# soundboard-qtpy-usd-dac-smaller-v02.net
KiCad netlist of a schematic drawn in EAGLE
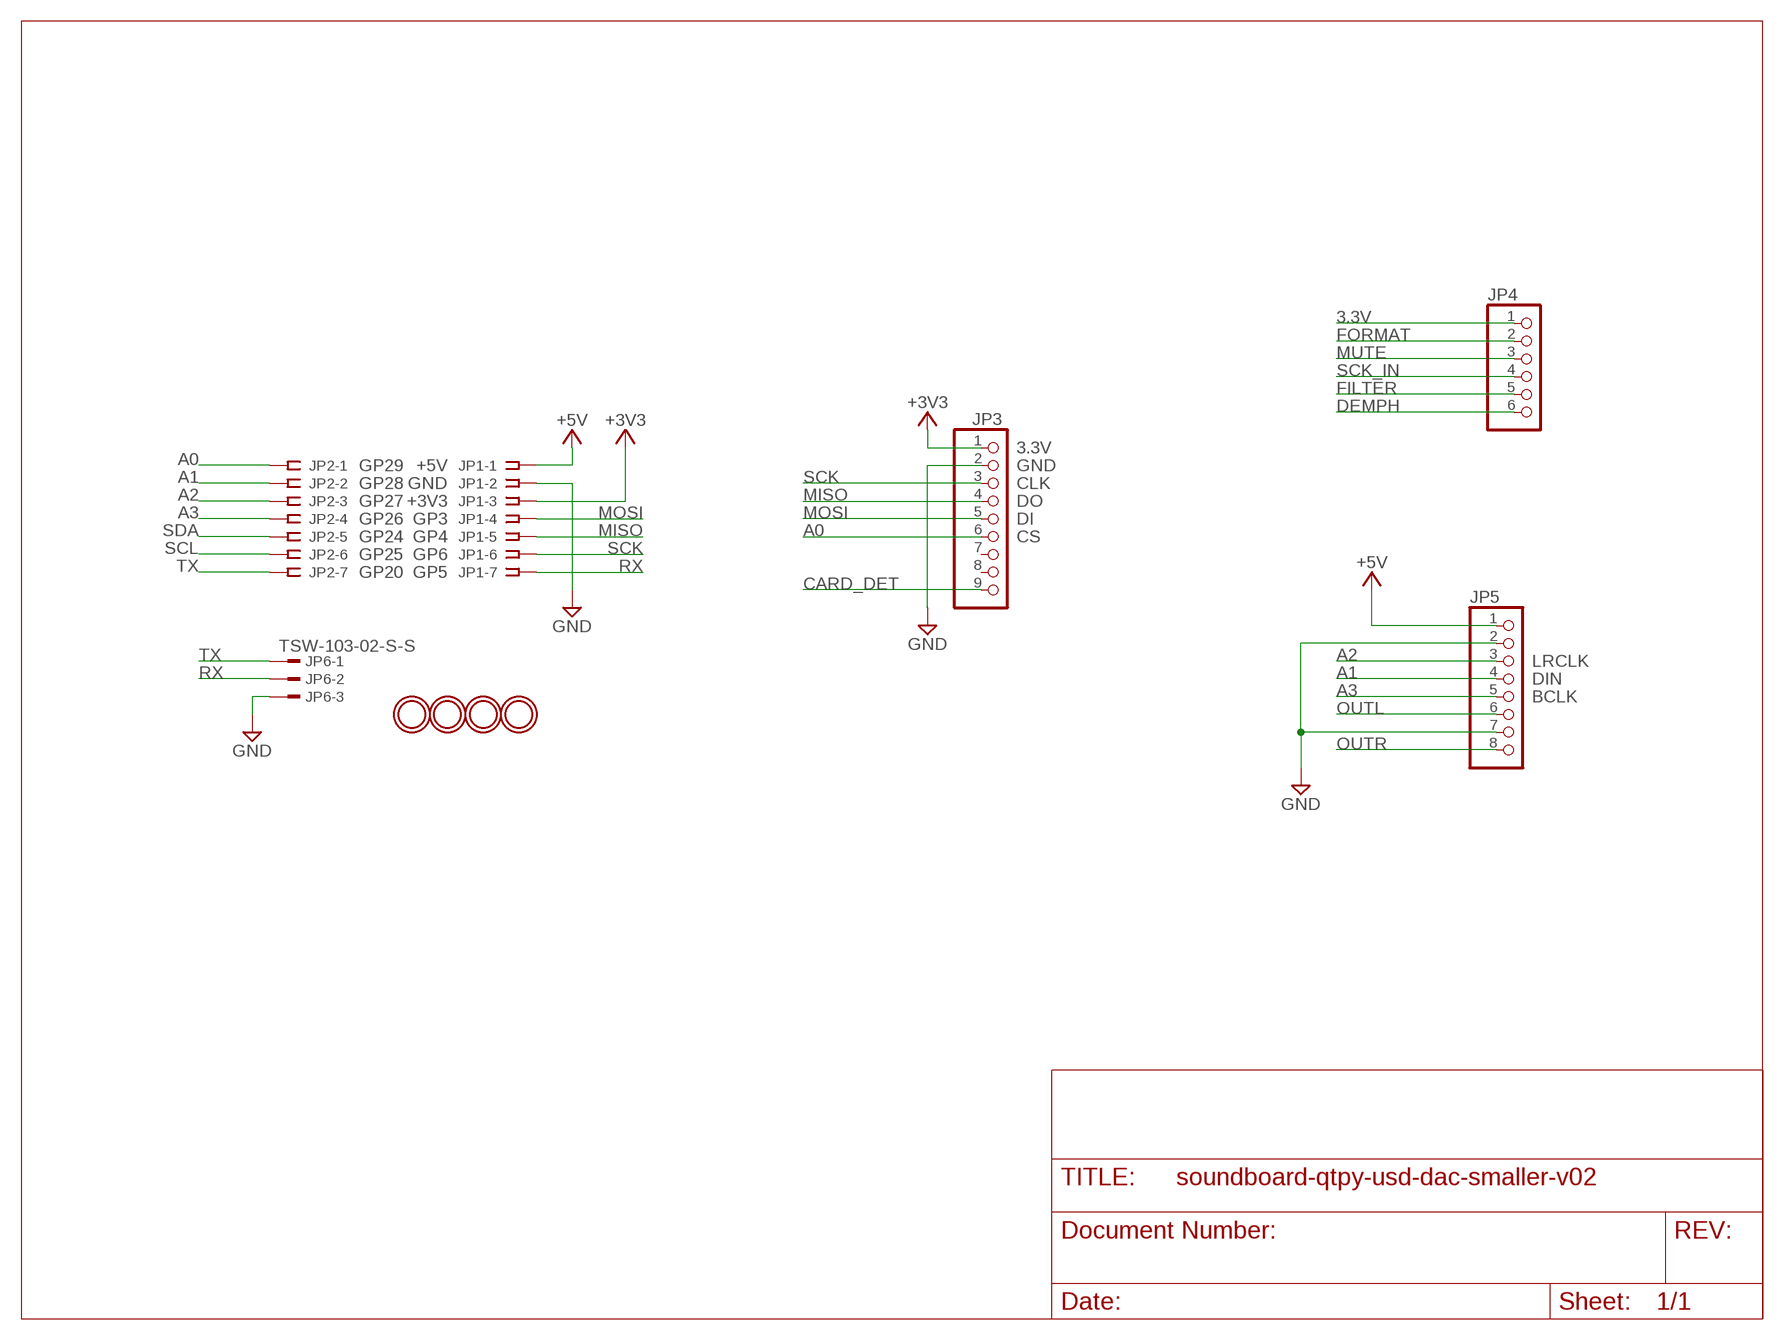
[diagram p0: schematic, sheet 1]

(export (version "E")
  (design (tool "Eeschema 10.0.6"))
  (components
    (comp (ref "JP1")
      (value "SSW-107-02-S-S")
      (footprint "eagle-import:SSW-107-02-S-S")
      (libsource (lib "eagle-import") (part "SSW-107-02-S-S"))
    )
    (comp (ref "JP2")
      (value "SSW-107-02-S-S")
      (footprint "eagle-import:SSW-107-02-S-S")
      (libsource (lib "eagle-import") (part "SSW-107-02-S-S"))
    )
    (comp (ref "JP3")
      (value "HEADER-1X970MIL")
      (footprint "eagle-import:1X09_ROUND_70")
      (libsource (lib "eagle-import") (part "HEADER-1X970MIL"))
    )
    (comp (ref "JP4")
      (value "HEADER-1X670MIL")
      (footprint "eagle-import:1X06_ROUND_70")
      (libsource (lib "eagle-import") (part "HEADER-1X670MIL"))
    )
    (comp (ref "JP5")
      (value "HEADER-1X8ROUND")
      (footprint "eagle-import:1X08_ROUND")
      (libsource (lib "eagle-import") (part "HEADER-1X8ROUND"))
    )
    (comp (ref "JP6")
      (value "TSW-103-02-S-S")
      (footprint "eagle-import:TSW-103-02-S-S")
      (libsource (lib "eagle-import") (part "TSW-103-02-S-S"))
    )
    (comp (ref "U$11")
      (value "MOUNTINGHOLE2.5")
      (footprint "eagle-import:MOUNTINGHOLE_2.5_PLATED")
      (libsource (lib "eagle-import") (part "MOUNTINGHOLE2.5"))
    )
    (comp (ref "U$12")
      (value "MOUNTINGHOLE2.5")
      (footprint "eagle-import:MOUNTINGHOLE_2.5_PLATED")
      (libsource (lib "eagle-import") (part "MOUNTINGHOLE2.5"))
    )
    (comp (ref "U$13")
      (value "MOUNTINGHOLE2.5")
      (footprint "eagle-import:MOUNTINGHOLE_2.5_PLATED")
      (libsource (lib "eagle-import") (part "MOUNTINGHOLE2.5"))
    )
    (comp (ref "U$14")
      (value "MOUNTINGHOLE2.5")
      (footprint "eagle-import:MOUNTINGHOLE_2.5_PLATED")
      (libsource (lib "eagle-import") (part "MOUNTINGHOLE2.5"))
    )
  )
  (nets
    (net (code "1") (name "+3V3") (class "Default")
      (node (ref "JP1") (pin "3") (pinfunction "1_3") (pintype "passive"))
      (node (ref "JP3") (pin "1") (pinfunction "1_1") (pintype "passive"))
    )
    (net (code "2") (name "+5V") (class "Default")
      (node (ref "JP1") (pin "1") (pinfunction "1_1") (pintype "passive"))
      (node (ref "JP5") (pin "1") (pinfunction "1_1") (pintype "passive"))
    )
    (net (code "3") (name "/3.3V") (class "Default")
      (node (ref "JP4") (pin "1") (pinfunction "1_1") (pintype "passive"))
    )
    (net (code "4") (name "/A0") (class "Default")
      (node (ref "JP2") (pin "1") (pinfunction "1_1") (pintype "passive"))
      (node (ref "JP3") (pin "6") (pinfunction "6_6") (pintype "passive"))
    )
    (net (code "5") (name "/A1") (class "Default")
      (node (ref "JP2") (pin "2") (pinfunction "1_2") (pintype "passive"))
      (node (ref "JP5") (pin "4") (pinfunction "4_4") (pintype "passive"))
    )
    (net (code "6") (name "/A2") (class "Default")
      (node (ref "JP2") (pin "3") (pinfunction "1_3") (pintype "passive"))
      (node (ref "JP5") (pin "3") (pinfunction "3_3") (pintype "passive"))
    )
    (net (code "7") (name "/A3") (class "Default")
      (node (ref "JP2") (pin "4") (pinfunction "1_4") (pintype "passive"))
      (node (ref "JP5") (pin "5") (pinfunction "5_5") (pintype "passive"))
    )
    (net (code "8") (name "/CARD_DET") (class "Default")
      (node (ref "JP3") (pin "9") (pinfunction "9_9") (pintype "passive"))
    )
    (net (code "9") (name "/DEMPH") (class "Default")
      (node (ref "JP4") (pin "6") (pinfunction "6_6") (pintype "passive"))
    )
    (net (code "10") (name "/FILTER") (class "Default")
      (node (ref "JP4") (pin "5") (pinfunction "5_5") (pintype "passive"))
    )
    (net (code "11") (name "/FORMAT") (class "Default")
      (node (ref "JP4") (pin "2") (pinfunction "2_2") (pintype "passive"))
    )
    (net (code "12") (name "/MISO") (class "Default")
      (node (ref "JP1") (pin "5") (pinfunction "1_5") (pintype "passive"))
      (node (ref "JP3") (pin "4") (pinfunction "4_4") (pintype "passive"))
    )
    (net (code "13") (name "/MOSI") (class "Default")
      (node (ref "JP1") (pin "4") (pinfunction "1_4") (pintype "passive"))
      (node (ref "JP3") (pin "5") (pinfunction "5_5") (pintype "passive"))
    )
    (net (code "14") (name "/MUTE") (class "Default")
      (node (ref "JP4") (pin "3") (pinfunction "3_3") (pintype "passive"))
    )
    (net (code "15") (name "/OUTL") (class "Default")
      (node (ref "JP5") (pin "6") (pinfunction "6_6") (pintype "passive"))
    )
    (net (code "16") (name "/OUTR") (class "Default")
      (node (ref "JP5") (pin "8") (pinfunction "8_8") (pintype "passive"))
    )
    (net (code "17") (name "/RX") (class "Default")
      (node (ref "JP1") (pin "7") (pinfunction "1_7") (pintype "passive"))
      (node (ref "JP6") (pin "2") (pinfunction "1_2") (pintype "passive"))
    )
    (net (code "18") (name "/SCK") (class "Default")
      (node (ref "JP1") (pin "6") (pinfunction "1_6") (pintype "passive"))
      (node (ref "JP3") (pin "3") (pinfunction "3_3") (pintype "passive"))
    )
    (net (code "19") (name "/SCK_IN") (class "Default")
      (node (ref "JP4") (pin "4") (pinfunction "4_4") (pintype "passive"))
    )
    (net (code "20") (name "/SCL") (class "Default")
      (node (ref "JP2") (pin "6") (pinfunction "1_6") (pintype "passive"))
    )
    (net (code "21") (name "/SDA") (class "Default")
      (node (ref "JP2") (pin "5") (pinfunction "1_5") (pintype "passive"))
    )
    (net (code "22") (name "/TX") (class "Default")
      (node (ref "JP2") (pin "7") (pinfunction "1_7") (pintype "passive"))
      (node (ref "JP6") (pin "1") (pinfunction "1_1") (pintype "passive"))
    )
    (net (code "23") (name "GND") (class "Default")
      (node (ref "JP1") (pin "2") (pinfunction "1_2") (pintype "passive"))
      (node (ref "JP3") (pin "2") (pinfunction "2_2") (pintype "passive"))
      (node (ref "JP5") (pin "2") (pinfunction "2_2") (pintype "passive"))
      (node (ref "JP5") (pin "7") (pinfunction "7_7") (pintype "passive"))
      (node (ref "JP6") (pin "3") (pinfunction "1_3") (pintype "passive"))
    )
    (net (code "24") (name "unconnected-(JP3-Pad7)") (class "Default")
      (node (ref "JP3") (pin "7") (pinfunction "7_7") (pintype "passive"))
    )
    (net (code "25") (name "unconnected-(JP3-Pad8)") (class "Default")
      (node (ref "JP3") (pin "8") (pinfunction "8_8") (pintype "passive"))
    )
  )
)
